# Eagle_TiltSwitch.net
KiCad netlist of a schematic drawn in EAGLE
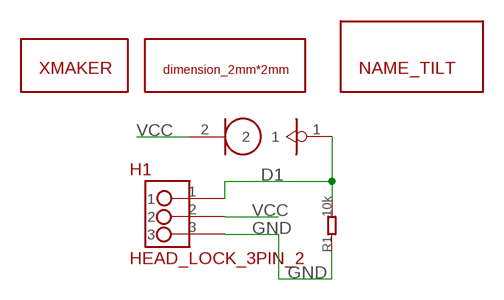
[diagram p0: schematic, sheet 1]

(export (version "E")
  (design (tool "Eeschema 10.0.6"))
  (components
    (comp (ref "H1")
      (value "HEAD_LOCK_3PIN_2")
      (footprint "eagle-import:HEAD_LOCK_3PIN_2")
      (libsource (lib "eagle-import") (part "HEAD_LOCK_3PIN_2"))
    )
    (comp (ref "J1")
      (value "TILT")
      (footprint "eagle-import:TILT")
      (libsource (lib "eagle-import") (part "TILT"))
    )
    (comp (ref "R1")
      (value "10k")
      (footprint "eagle-import:0603")
      (libsource (lib "eagle-import") (part "005-R0603"))
    )
    (comp (ref "U$2")
      (value "XMAKERLOGO")
      (footprint "eagle-import:XMAKERLOGO")
      (libsource (lib "eagle-import") (part "XMAKERLOGO"))
    )
    (comp (ref "U$3")
      (value "DIMENSION_2MM2MM")
      (footprint "eagle-import:DIMENSION_2MM_2MM")
      (libsource (lib "eagle-import") (part "DIMENSION_2MM2MM"))
    )
    (comp (ref "U$4")
      (value "NAME_LILT")
      (footprint "eagle-import:NAME_TILT")
      (libsource (lib "eagle-import") (part "NAME_LILT"))
    )
  )
  (nets
    (net (code "1") (name "/D1") (class "Default")
      (node (ref "H1") (pin "1") (pinfunction "1_1") (pintype "passive"))
      (node (ref "J1") (pin "1") (pinfunction "1_1") (pintype "bidirectional"))
      (node (ref "R1") (pin "2") (pinfunction "2_2") (pintype "passive"))
    )
    (net (code "2") (name "/GND") (class "Default")
      (node (ref "H1") (pin "3") (pinfunction "3_3") (pintype "passive"))
      (node (ref "R1") (pin "1") (pinfunction "1_1") (pintype "passive"))
    )
    (net (code "3") (name "/VCC") (class "Default")
      (node (ref "H1") (pin "2") (pinfunction "2_2") (pintype "passive"))
      (node (ref "J1") (pin "2") (pinfunction "2_2") (pintype "bidirectional"))
    )
  )
)
